# 3_-ADC.net
KiCad netlist of a schematic drawn in Altium Designer
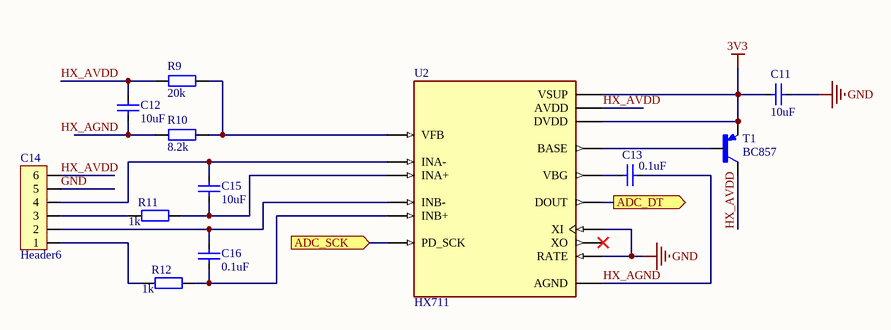
[diagram p0: [3]-ADC.SchDoc]

(export (version "E")
  (design (tool "Eeschema 10.0.6"))
  (components
    (comp (ref "C11")
      (value "10uF")
      (footprint "CAP_0805")
      (description "Capacitor")
      (fields (field (name "PUBLISHER") "Altium Limited"))
      (libsource (lib "My Library") (part "CapSMD"))
    )
    (comp (ref "C12")
      (value "10uF")
      (footprint "CAP_0805")
      (description "Capacitor")
      (fields (field (name "PUBLISHER") "Altium Limited"))
      (libsource (lib "My Library") (part "CapSMD"))
    )
    (comp (ref "C13")
      (value "0.1uF")
      (footprint "CAP_0805")
      (description "Capacitor")
      (fields (field (name "PUBLISHER") "Altium Limited"))
      (libsource (lib "My Library") (part "CapSMD"))
    )
    (comp (ref "C14")
      (value "Header6")
      (footprint "CON6")
      (description "Header IDC, 6 x 1 Pin Vertical 2.54mm Pitch (Non-Boxed, Male)")
      (fields
        (field (name "MANUFACTURER") "Würth Elektronik eiSos GmbH")
        (field (name "PARTNO") "613002143121")
        (field (name "CREATED BY") "Karrer Zheng")
      )
      (libsource (lib "My Library") (part "Header6"))
    )
    (comp (ref "C15")
      (value "10uF")
      (footprint "CAP_0805")
      (description "Capacitor")
      (fields (field (name "PUBLISHER") "Altium Limited"))
      (libsource (lib "My Library") (part "CapSMD"))
    )
    (comp (ref "C16")
      (value "0.1uF")
      (footprint "CAP_0805")
      (description "Capacitor")
      (fields (field (name "PUBLISHER") "Altium Limited"))
      (libsource (lib "My Library") (part "CapSMD"))
    )
    (comp (ref "R9")
      (value "20k")
      (footprint "RES-SMD-0805")
      (description "Resistor SMD")
      (fields
        (field (name "MANUFACTURER") "Generic Components")
        (field (name "PUBLISHER") "Altium Hobart Technology Centre")
      )
      (libsource (lib "My Library") (part "Resistor - SMD"))
    )
    (comp (ref "R10")
      (value "8.2k")
      (footprint "RES-SMD-0805")
      (description "Resistor SMD")
      (fields
        (field (name "MANUFACTURER") "Generic Components")
        (field (name "PUBLISHER") "Altium Hobart Technology Centre")
      )
      (libsource (lib "My Library") (part "Resistor - SMD"))
    )
    (comp (ref "R11")
      (value "1k")
      (footprint "RES-SMD-0805")
      (description "Resistor SMD")
      (fields
        (field (name "MANUFACTURER") "Generic Components")
        (field (name "PUBLISHER") "Altium Hobart Technology Centre")
      )
      (libsource (lib "My Library") (part "Resistor - SMD"))
    )
    (comp (ref "R12")
      (value "1k")
      (footprint "RES-SMD-0805")
      (description "Resistor SMD")
      (fields
        (field (name "MANUFACTURER") "Generic Components")
        (field (name "PUBLISHER") "Altium Hobart Technology Centre")
      )
      (libsource (lib "My Library") (part "Resistor - SMD"))
    )
    (comp (ref "T1")
      (value "BC857")
      (footprint "SOT23-BEC")
      (description "Transistor PNP BC857 PHILIPS Ampere=1 V=30 SO")
      (fields (field (name "MF") "Nexperia USA"))
      (libsource (lib "BC857") (part "BC857"))
    )
    (comp (ref "U2")
      (value "HX711")
      (footprint "SOP127P600X180-16N")
      (fields (field (name "MF") "AVIA SEMICONDUCTOR"))
      (libsource (lib "HX711") (part "HX711"))
    )
  )
  (nets
    (net (code "1") (name "/ADC_DT") (class "Default")
      (node (ref "U2") (pin "12") (pinfunction "DOUT_12") (pintype "output"))
    )
    (net (code "2") (name "/ADC_SCK") (class "Default")
      (node (ref "U2") (pin "11") (pinfunction "PD_SCK_11") (pintype "input"))
    )
    (net (code "3") (name "/HX_AGND") (class "Default")
      (node (ref "C13") (pin "1") (pinfunction "1_1") (pintype "passive"))
      (node (ref "U2") (pin "5") (pinfunction "AGND_5") (pintype "power_in"))
    )
    (net (code "4") (name "/HX_AVDD") (class "Default")
      (node (ref "C12") (pin "2") (pinfunction "2_2") (pintype "passive"))
      (node (ref "C14") (pin "6") (pinfunction "6_6") (pintype "passive"))
      (node (ref "R9") (pin "1") (pinfunction "1_1") (pintype "passive"))
      (node (ref "T1") (pin "C") (pinfunction "C_C") (pintype "passive"))
      (node (ref "U2") (pin "3") (pinfunction "AVDD_3") (pintype "power_in"))
    )
    (net (code "5") (name "3V3") (class "Default")
      (node (ref "C11") (pin "2") (pinfunction "2_2") (pintype "passive"))
      (node (ref "T1") (pin "E") (pinfunction "E_E") (pintype "passive"))
      (node (ref "U2") (pin "1") (pinfunction "VSUP_1") (pintype "power_in"))
      (node (ref "U2") (pin "16") (pinfunction "DVDD_16") (pintype "power_in"))
    )
    (net (code "6") (name "GND") (class "Default")
      (node (ref "C11") (pin "1") (pinfunction "1_1") (pintype "passive"))
      (node (ref "C14") (pin "5") (pinfunction "5_5") (pintype "passive"))
      (node (ref "U2") (pin "14") (pinfunction "XI_14") (pintype "input"))
      (node (ref "U2") (pin "15") (pinfunction "RATE_15") (pintype "input"))
    )
    (net (code "7") (name "Net-(C12-Pad1)") (class "Default")
      (node (ref "C12") (pin "1") (pinfunction "1_1") (pintype "passive"))
      (node (ref "R10") (pin "1") (pinfunction "1_1") (pintype "passive"))
    )
    (net (code "8") (name "Net-(C14-Pad1)") (class "Default")
      (node (ref "C14") (pin "1") (pinfunction "1_1") (pintype "passive"))
      (node (ref "R12") (pin "1") (pinfunction "1_1") (pintype "passive"))
    )
    (net (code "9") (name "Net-(C14-Pad3)") (class "Default")
      (node (ref "C14") (pin "3") (pinfunction "3_3") (pintype "passive"))
      (node (ref "R11") (pin "1") (pinfunction "1_1") (pintype "passive"))
    )
    (net (code "10") (name "Net-(U2-BASE)") (class "Default")
      (node (ref "T1") (pin "B") (pinfunction "B_B") (pintype "passive"))
      (node (ref "U2") (pin "2") (pinfunction "BASE_2") (pintype "output"))
    )
    (net (code "11") (name "Net-(U2-INA+)") (class "Default")
      (node (ref "C15") (pin "1") (pinfunction "1_1") (pintype "passive"))
      (node (ref "R11") (pin "2") (pinfunction "2_2") (pintype "passive"))
      (node (ref "U2") (pin "8") (pinfunction "INA+_8") (pintype "input"))
    )
    (net (code "12") (name "Net-(U2-INA-)") (class "Default")
      (node (ref "C14") (pin "4") (pinfunction "4_4") (pintype "passive"))
      (node (ref "C15") (pin "2") (pinfunction "2_2") (pintype "passive"))
      (node (ref "U2") (pin "7") (pinfunction "INA-_7") (pintype "input"))
    )
    (net (code "13") (name "Net-(U2-INB+)") (class "Default")
      (node (ref "C16") (pin "1") (pinfunction "1_1") (pintype "passive"))
      (node (ref "R12") (pin "2") (pinfunction "2_2") (pintype "passive"))
      (node (ref "U2") (pin "10") (pinfunction "INB+_10") (pintype "input"))
    )
    (net (code "14") (name "Net-(U2-INB-)") (class "Default")
      (node (ref "C14") (pin "2") (pinfunction "2_2") (pintype "passive"))
      (node (ref "C16") (pin "2") (pinfunction "2_2") (pintype "passive"))
      (node (ref "U2") (pin "9") (pinfunction "INB-_9") (pintype "input"))
    )
    (net (code "15") (name "Net-(U2-VBG)") (class "Default")
      (node (ref "C13") (pin "2") (pinfunction "2_2") (pintype "passive"))
      (node (ref "U2") (pin "6") (pinfunction "VBG_6") (pintype "output"))
    )
    (net (code "16") (name "Net-(U2-VFB)") (class "Default")
      (node (ref "R10") (pin "2") (pinfunction "2_2") (pintype "passive"))
      (node (ref "R9") (pin "2") (pinfunction "2_2") (pintype "passive"))
      (node (ref "U2") (pin "4") (pinfunction "VFB_4") (pintype "input"))
    )
    (net (code "17") (name "unconnected-(U2-XO-Pad13)") (class "Default")
      (node (ref "U2") (pin "13") (pinfunction "XO_13") (pintype "output+no_connect"))
    )
  )
)
